# LWK2_MainBoard_Rev_1.net
KiCad netlist of a schematic drawn in EAGLE
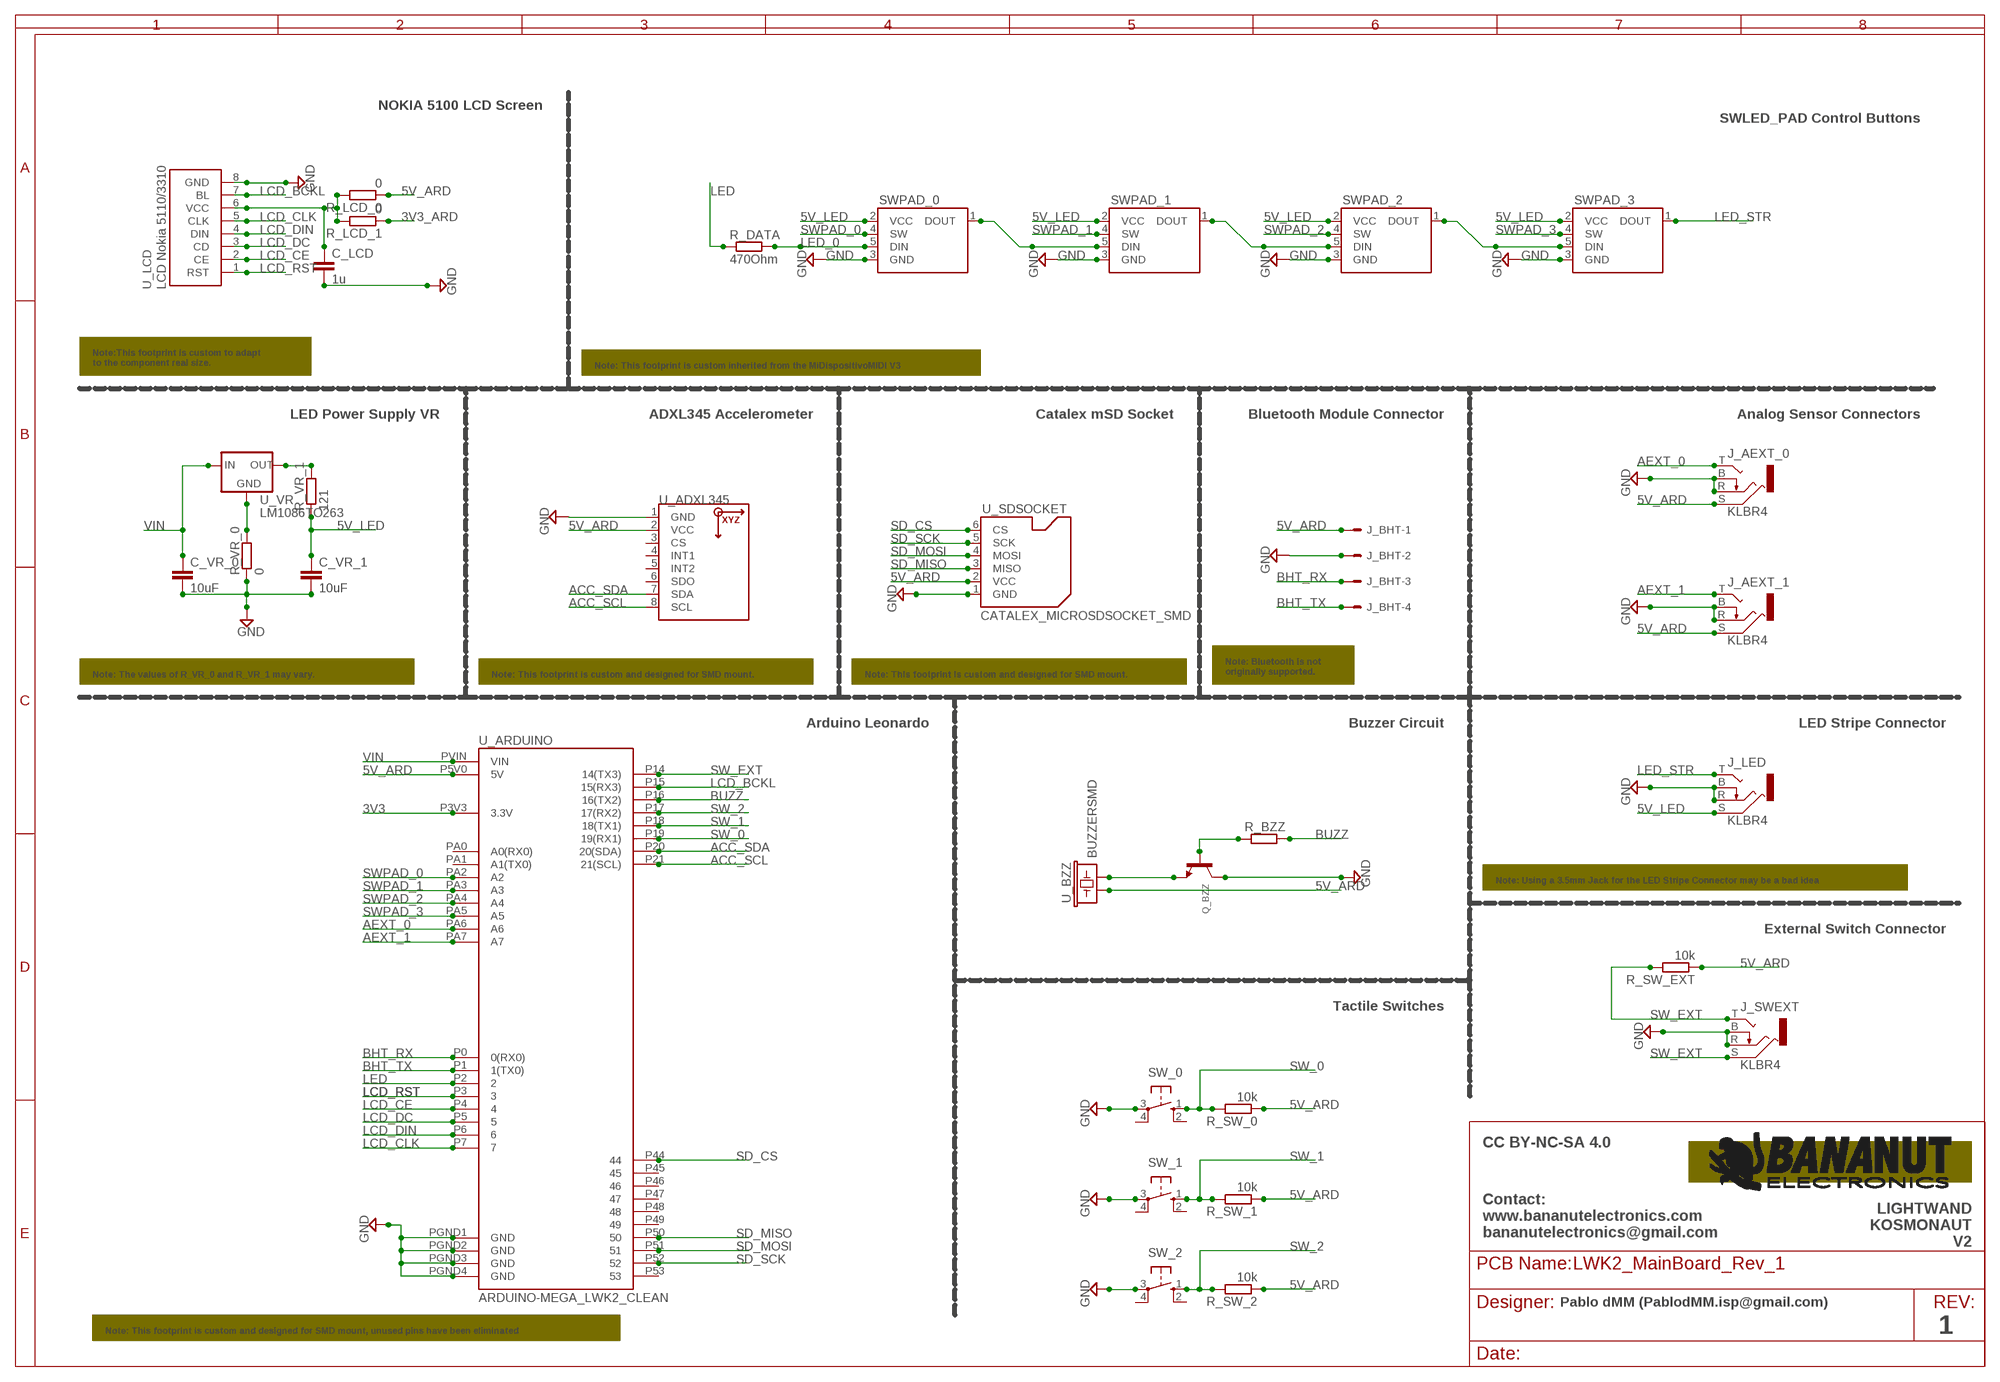
[diagram p0: schematic, sheet 1]

(export (version "E")
  (design (tool "Eeschema 10.0.6"))
  (components
    (comp (ref "C_LCD")
      (value "1u")
      (footprint "eagle-import:C1206")
      (libsource (lib "eagle-import") (part "C-EUC1206"))
    )
    (comp (ref "C_VR_0")
      (value "10uF")
      (footprint "eagle-import:C1206")
      (libsource (lib "eagle-import") (part "C-EUC1206"))
    )
    (comp (ref "C_VR_1")
      (value "10uF")
      (footprint "eagle-import:C1206")
      (libsource (lib "eagle-import") (part "C-EUC1206"))
    )
    (comp (ref "J_AEXT_0")
      (value "KLBR4")
      (footprint "eagle-import:KLBR4")
      (fields (field (name "MPN") "KLBR 4"))
      (libsource (lib "eagle-import") (part "KLBR4"))
    )
    (comp (ref "J_AEXT_1")
      (value "KLBR4")
      (footprint "eagle-import:KLBR4")
      (fields (field (name "MPN") "KLBR 4"))
      (libsource (lib "eagle-import") (part "KLBR4"))
    )
    (comp (ref "J_BHT")
      (value "22-05-7048-04")
      (footprint "eagle-import:7395-04")
      (libsource (lib "eagle-import") (part "22-?-0405-7048"))
    )
    (comp (ref "J_LED")
      (value "KLBR4")
      (footprint "eagle-import:KLBR4")
      (fields (field (name "MPN") "KLBR 4"))
      (libsource (lib "eagle-import") (part "KLBR4"))
    )
    (comp (ref "J_SWEXT")
      (value "KLBR4")
      (footprint "eagle-import:KLBR4")
      (fields (field (name "MPN") "KLBR 4"))
      (libsource (lib "eagle-import") (part "KLBR4"))
    )
    (comp (ref "Q_BZZ")
      (value "TRANSISTOR_NPNWIDE")
      (footprint "eagle-import:SOT23-WIDE")
      (libsource (lib "eagle-import") (part "TRANSISTOR_NPNWIDE"))
    )
    (comp (ref "R_BZZ")
      (value "R-EU_R1206")
      (footprint "eagle-import:R1206")
      (libsource (lib "eagle-import") (part "R-EU_R1206"))
    )
    (comp (ref "R_DATA")
      (value "470Ohm")
      (footprint "eagle-import:R1206")
      (libsource (lib "eagle-import") (part "R-EU_R1206"))
    )
    (comp (ref "R_LCD_0")
      (value "0")
      (footprint "eagle-import:R1206")
      (libsource (lib "eagle-import") (part "R-EU_R1206"))
    )
    (comp (ref "R_LCD_1")
      (value "0")
      (footprint "eagle-import:R1206")
      (libsource (lib "eagle-import") (part "R-EU_R1206"))
    )
    (comp (ref "R_SW_0")
      (value "10k")
      (footprint "eagle-import:R1206")
      (libsource (lib "eagle-import") (part "R-EU_R1206"))
    )
    (comp (ref "R_SW_1")
      (value "10k")
      (footprint "eagle-import:R1206")
      (libsource (lib "eagle-import") (part "R-EU_R1206"))
    )
    (comp (ref "R_SW_2")
      (value "10k")
      (footprint "eagle-import:R1206")
      (libsource (lib "eagle-import") (part "R-EU_R1206"))
    )
    (comp (ref "R_SW_EXT")
      (value "10k")
      (footprint "eagle-import:R1206")
      (libsource (lib "eagle-import") (part "R-EU_R1206"))
    )
    (comp (ref "R_VR_0")
      (value "0")
      (footprint "eagle-import:R1206")
      (libsource (lib "eagle-import") (part "R-EU_R1206"))
    )
    (comp (ref "R_VR_1")
      (value "121")
      (footprint "eagle-import:R1206")
      (libsource (lib "eagle-import") (part "R-EU_R1206"))
    )
    (comp (ref "SWPAD_0")
      (value "MDM_V3_LEDPAD")
      (footprint "eagle-import:MDM_V3_LEDPAD")
      (libsource (lib "eagle-import") (part "MDM_V3_LEDPAD"))
    )
    (comp (ref "SWPAD_1")
      (value "MDM_V3_LEDPAD")
      (footprint "eagle-import:MDM_V3_LEDPAD")
      (libsource (lib "eagle-import") (part "MDM_V3_LEDPAD"))
    )
    (comp (ref "SWPAD_2")
      (value "MDM_V3_LEDPAD")
      (footprint "eagle-import:MDM_V3_LEDPAD")
      (libsource (lib "eagle-import") (part "MDM_V3_LEDPAD"))
    )
    (comp (ref "SWPAD_3")
      (value "MDM_V3_LEDPAD")
      (footprint "eagle-import:MDM_V3_LEDPAD")
      (libsource (lib "eagle-import") (part "MDM_V3_LEDPAD"))
    )
    (comp (ref "SW_0")
      (value "40-XX-ROUND")
      (footprint "eagle-import:B3F-40XX-ROUND")
      (libsource (lib "eagle-import") (part "40-XX-ROUND"))
    )
    (comp (ref "SW_1")
      (value "40-XX-ROUND")
      (footprint "eagle-import:B3F-40XX-ROUND")
      (libsource (lib "eagle-import") (part "40-XX-ROUND"))
    )
    (comp (ref "SW_2")
      (value "40-XX-ROUND")
      (footprint "eagle-import:B3F-40XX-ROUND")
      (libsource (lib "eagle-import") (part "40-XX-ROUND"))
    )
    (comp (ref "U_ADXL345")
      (value "GY-291_ADXL345")
      (footprint "eagle-import:GY-291_ADXL345")
      (libsource (lib "eagle-import") (part "GY-291_ADXL345"))
    )
    (comp (ref "U_ARDUINO")
      (value "ARDUINO-MEGA_LWK2_CLEAN")
      (footprint "eagle-import:ARDUINO_MEGA_LWK2_CLEAN")
      (libsource (lib "eagle-import") (part "ARDUINO-MEGA_LWK2_CLEAN"))
    )
    (comp (ref "U_BZZ")
      (value "BUZZERSMD")
      (footprint "eagle-import:BUZZER-CMT1603")
      (libsource (lib "eagle-import") (part "BUZZERSMD"))
    )
    (comp (ref "U_LCD")
      (value "NOKIA5110")
      (footprint "eagle-import:NOKIA5110")
      (libsource (lib "eagle-import") (part "NOKIA5110"))
    )
    (comp (ref "U_SDSOCKET")
      (value "CATALEX_MICROSDSOCKET_SMD")
      (footprint "eagle-import:CATALEX_MICROSDSOCKET_SMD")
      (libsource (lib "eagle-import") (part "CATALEX_MICROSDSOCKET_SMD"))
    )
    (comp (ref "U_VR")
      (value "LM1086TO263")
      (footprint "eagle-import:TO263")
      (libsource (lib "eagle-import") (part "LM1086TO263"))
    )
  )
  (nets
    (net (code "1") (name "/3V3") (class "Default")
      (node (ref "U_ARDUINO") (pin "P3V3") (pinfunction "3.3V_P3V3") (pintype "bidirectional"))
    )
    (net (code "2") (name "/3V3_ARD") (class "Default")
      (node (ref "R_LCD_1") (pin "1") (pinfunction "1_1") (pintype "passive"))
    )
    (net (code "3") (name "/5V_ARD") (class "Default")
      (node (ref "J_AEXT_0") (pin "S") (pinfunction "S_S") (pintype "passive"))
      (node (ref "J_AEXT_1") (pin "S") (pinfunction "S_S") (pintype "passive"))
      (node (ref "J_BHT") (pin "1") (pinfunction "S_1") (pintype "passive"))
      (node (ref "R_LCD_0") (pin "1") (pinfunction "1_1") (pintype "passive"))
      (node (ref "R_SW_0") (pin "1") (pinfunction "1_1") (pintype "passive"))
      (node (ref "R_SW_1") (pin "1") (pinfunction "1_1") (pintype "passive"))
      (node (ref "R_SW_2") (pin "1") (pinfunction "1_1") (pintype "passive"))
      (node (ref "R_SW_EXT") (pin "1") (pinfunction "1_1") (pintype "passive"))
      (node (ref "U_ADXL345") (pin "2") (pinfunction "VCC_2") (pintype "output"))
      (node (ref "U_ARDUINO") (pin "P5V0") (pinfunction "5V_P5V0") (pintype "bidirectional"))
      (node (ref "U_BZZ") (pin "P$1") (pinfunction "1_P$1") (pintype "passive"))
      (node (ref "U_SDSOCKET") (pin "2") (pinfunction "VCC_2") (pintype "output"))
    )
    (net (code "4") (name "/5V_LED") (class "Default")
      (node (ref "C_VR_1") (pin "1") (pinfunction "1_1") (pintype "passive"))
      (node (ref "J_LED") (pin "S") (pinfunction "S_S") (pintype "passive"))
      (node (ref "R_VR_1") (pin "1") (pinfunction "1_1") (pintype "passive"))
      (node (ref "SWPAD_0") (pin "2") (pinfunction "VCC_2") (pintype "power_in"))
      (node (ref "SWPAD_1") (pin "2") (pinfunction "VCC_2") (pintype "power_in"))
      (node (ref "SWPAD_2") (pin "2") (pinfunction "VCC_2") (pintype "power_in"))
      (node (ref "SWPAD_3") (pin "2") (pinfunction "VCC_2") (pintype "power_in"))
    )
    (net (code "5") (name "/ACC_SCL") (class "Default")
      (node (ref "U_ADXL345") (pin "8") (pinfunction "SCL_8") (pintype "power_in"))
      (node (ref "U_ARDUINO") (pin "P21") (pinfunction "21(SCL)_P21") (pintype "bidirectional"))
    )
    (net (code "6") (name "/ACC_SDA") (class "Default")
      (node (ref "U_ADXL345") (pin "7") (pinfunction "SDA_7") (pintype "power_in"))
      (node (ref "U_ARDUINO") (pin "P20") (pinfunction "20(SDA)_P20") (pintype "bidirectional"))
    )
    (net (code "7") (name "/AEXT_0") (class "Default")
      (node (ref "J_AEXT_0") (pin "T") (pinfunction "T_T") (pintype "passive"))
      (node (ref "U_ARDUINO") (pin "PA6") (pinfunction "A6_PA6") (pintype "bidirectional"))
    )
    (net (code "8") (name "/AEXT_1") (class "Default")
      (node (ref "J_AEXT_1") (pin "T") (pinfunction "T_T") (pintype "passive"))
      (node (ref "U_ARDUINO") (pin "PA7") (pinfunction "A7_PA7") (pintype "bidirectional"))
    )
    (net (code "9") (name "/BHT_RX") (class "Default")
      (node (ref "J_BHT") (pin "3") (pinfunction "S_3") (pintype "passive"))
      (node (ref "U_ARDUINO") (pin "P0") (pinfunction "0(RX0)_P0") (pintype "bidirectional"))
    )
    (net (code "10") (name "/BHT_TX") (class "Default")
      (node (ref "J_BHT") (pin "4") (pinfunction "S_4") (pintype "passive"))
      (node (ref "U_ARDUINO") (pin "P1") (pinfunction "1(TX0)_P1") (pintype "bidirectional"))
    )
    (net (code "11") (name "/BUZZ") (class "Default")
      (node (ref "R_BZZ") (pin "2") (pinfunction "2_2") (pintype "passive"))
      (node (ref "U_ARDUINO") (pin "P16") (pinfunction "16(TX2)_P16") (pintype "bidirectional"))
    )
    (net (code "12") (name "/CS") (class "Default")
      (node (ref "U_ADXL345") (pin "3") (pinfunction "CS_3") (pintype "power_in"))
    )
    (net (code "13") (name "/INT1") (class "Default")
      (node (ref "U_ADXL345") (pin "4") (pinfunction "INT1_4") (pintype "power_in"))
    )
    (net (code "14") (name "/INT2") (class "Default")
      (node (ref "U_ADXL345") (pin "5") (pinfunction "INT2_5") (pintype "power_in"))
    )
    (net (code "15") (name "/LCD_BCKL") (class "Default")
      (node (ref "U_ARDUINO") (pin "P15") (pinfunction "15(RX3)_P15") (pintype "bidirectional"))
      (node (ref "U_LCD") (pin "7") (pinfunction "BL_7") (pintype "bidirectional"))
    )
    (net (code "16") (name "/LCD_CE") (class "Default")
      (node (ref "U_ARDUINO") (pin "P4") (pinfunction "4_P4") (pintype "bidirectional"))
      (node (ref "U_LCD") (pin "2") (pinfunction "CE_2") (pintype "bidirectional"))
    )
    (net (code "17") (name "/LCD_CLK") (class "Default")
      (node (ref "U_ARDUINO") (pin "P7") (pinfunction "7_P7") (pintype "bidirectional"))
      (node (ref "U_LCD") (pin "5") (pinfunction "CLK_5") (pintype "bidirectional"))
    )
    (net (code "18") (name "/LCD_DC") (class "Default")
      (node (ref "U_ARDUINO") (pin "P5") (pinfunction "5_P5") (pintype "bidirectional"))
      (node (ref "U_LCD") (pin "3") (pinfunction "CD_3") (pintype "bidirectional"))
    )
    (net (code "19") (name "/LCD_DIN") (class "Default")
      (node (ref "U_ARDUINO") (pin "P6") (pinfunction "6_P6") (pintype "bidirectional"))
      (node (ref "U_LCD") (pin "4") (pinfunction "DIN_4") (pintype "bidirectional"))
    )
    (net (code "20") (name "/LCD_RST") (class "Default")
      (node (ref "U_ARDUINO") (pin "P3") (pinfunction "3_P3") (pintype "bidirectional"))
      (node (ref "U_LCD") (pin "1") (pinfunction "RST_1") (pintype "bidirectional"))
    )
    (net (code "21") (name "/LED") (class "Default")
      (node (ref "R_DATA") (pin "1") (pinfunction "1_1") (pintype "passive"))
      (node (ref "U_ARDUINO") (pin "P2") (pinfunction "2_P2") (pintype "bidirectional"))
    )
    (net (code "22") (name "/LED_0") (class "Default")
      (node (ref "R_DATA") (pin "2") (pinfunction "2_2") (pintype "passive"))
      (node (ref "SWPAD_0") (pin "5") (pinfunction "DIN_5") (pintype "input"))
    )
    (net (code "23") (name "/LED_STR") (class "Default")
      (node (ref "J_LED") (pin "T") (pinfunction "T_T") (pintype "passive"))
      (node (ref "SWPAD_3") (pin "1") (pinfunction "DOUT_1") (pintype "output"))
    )
    (net (code "24") (name "/SDO") (class "Default")
      (node (ref "U_ADXL345") (pin "6") (pinfunction "SDO_6") (pintype "power_in"))
    )
    (net (code "25") (name "/SD_CS") (class "Default")
      (node (ref "U_ARDUINO") (pin "P44") (pinfunction "44_P44") (pintype "bidirectional"))
      (node (ref "U_SDSOCKET") (pin "6") (pinfunction "CS_6") (pintype "power_in"))
    )
    (net (code "26") (name "/SD_MISO") (class "Default")
      (node (ref "U_ARDUINO") (pin "P50") (pinfunction "50_P50") (pintype "bidirectional"))
      (node (ref "U_SDSOCKET") (pin "3") (pinfunction "MISO_3") (pintype "power_in"))
    )
    (net (code "27") (name "/SD_MOSI") (class "Default")
      (node (ref "U_ARDUINO") (pin "P51") (pinfunction "51_P51") (pintype "bidirectional"))
      (node (ref "U_SDSOCKET") (pin "4") (pinfunction "MOSI_4") (pintype "input"))
    )
    (net (code "28") (name "/SD_SCK") (class "Default")
      (node (ref "U_ARDUINO") (pin "P52") (pinfunction "52_P52") (pintype "bidirectional"))
      (node (ref "U_SDSOCKET") (pin "5") (pinfunction "SCK_5") (pintype "input"))
    )
    (net (code "29") (name "/SWPAD_0") (class "Default")
      (node (ref "SWPAD_0") (pin "4") (pinfunction "SW_4") (pintype "input"))
      (node (ref "U_ARDUINO") (pin "PA2") (pinfunction "A2_PA2") (pintype "bidirectional"))
    )
    (net (code "30") (name "/SWPAD_1") (class "Default")
      (node (ref "SWPAD_1") (pin "4") (pinfunction "SW_4") (pintype "input"))
      (node (ref "U_ARDUINO") (pin "PA3") (pinfunction "A3_PA3") (pintype "bidirectional"))
    )
    (net (code "31") (name "/SWPAD_2") (class "Default")
      (node (ref "SWPAD_2") (pin "4") (pinfunction "SW_4") (pintype "input"))
      (node (ref "U_ARDUINO") (pin "PA4") (pinfunction "A4_PA4") (pintype "bidirectional"))
    )
    (net (code "32") (name "/SWPAD_3") (class "Default")
      (node (ref "SWPAD_3") (pin "4") (pinfunction "SW_4") (pintype "input"))
      (node (ref "U_ARDUINO") (pin "PA5") (pinfunction "A5_PA5") (pintype "bidirectional"))
    )
    (net (code "33") (name "/SW_0") (class "Default")
      (node (ref "R_SW_0") (pin "2") (pinfunction "2_2") (pintype "passive"))
      (node (ref "SW_0") (pin "1") (pinfunction "S_1") (pintype "passive"))
      (node (ref "U_ARDUINO") (pin "P19") (pinfunction "19(RX1)_P19") (pintype "bidirectional"))
    )
    (net (code "34") (name "/SW_1") (class "Default")
      (node (ref "R_SW_1") (pin "2") (pinfunction "2_2") (pintype "passive"))
      (node (ref "SW_1") (pin "1") (pinfunction "S_1") (pintype "passive"))
      (node (ref "U_ARDUINO") (pin "P18") (pinfunction "18(TX1)_P18") (pintype "bidirectional"))
    )
    (net (code "35") (name "/SW_2") (class "Default")
      (node (ref "R_SW_2") (pin "2") (pinfunction "2_2") (pintype "passive"))
      (node (ref "SW_2") (pin "1") (pinfunction "S_1") (pintype "passive"))
      (node (ref "U_ARDUINO") (pin "P17") (pinfunction "17(RX2)_P17") (pintype "bidirectional"))
    )
    (net (code "36") (name "/SW_EXT") (class "Default")
      (node (ref "J_SWEXT") (pin "S") (pinfunction "S_S") (pintype "passive"))
      (node (ref "J_SWEXT") (pin "T") (pinfunction "T_T") (pintype "passive"))
      (node (ref "R_SW_EXT") (pin "2") (pinfunction "2_2") (pintype "passive"))
      (node (ref "U_ARDUINO") (pin "P14") (pinfunction "14(TX3)_P14") (pintype "bidirectional"))
    )
    (net (code "37") (name "/VIN") (class "Default")
      (node (ref "C_VR_0") (pin "1") (pinfunction "1_1") (pintype "passive"))
      (node (ref "U_ARDUINO") (pin "PVIN") (pinfunction "VIN_PVIN") (pintype "bidirectional"))
      (node (ref "U_VR") (pin "3") (pinfunction "IN_3") (pintype "input"))
    )
    (net (code "38") (name "GND") (class "Default")
      (node (ref "C_LCD") (pin "2") (pinfunction "2_2") (pintype "passive"))
      (node (ref "C_VR_0") (pin "2") (pinfunction "2_2") (pintype "passive"))
      (node (ref "C_VR_1") (pin "2") (pinfunction "2_2") (pintype "passive"))
      (node (ref "J_AEXT_0") (pin "B") (pinfunction "B_B") (pintype "passive"))
      (node (ref "J_AEXT_0") (pin "R") (pinfunction "R_R") (pintype "passive"))
      (node (ref "J_AEXT_1") (pin "B") (pinfunction "B_B") (pintype "passive"))
      (node (ref "J_AEXT_1") (pin "R") (pinfunction "R_R") (pintype "passive"))
      (node (ref "J_BHT") (pin "2") (pinfunction "S_2") (pintype "passive"))
      (node (ref "J_LED") (pin "B") (pinfunction "B_B") (pintype "passive"))
      (node (ref "J_LED") (pin "R") (pinfunction "R_R") (pintype "passive"))
      (node (ref "J_SWEXT") (pin "B") (pinfunction "B_B") (pintype "passive"))
      (node (ref "J_SWEXT") (pin "R") (pinfunction "R_R") (pintype "passive"))
      (node (ref "Q_BZZ") (pin "3") (pinfunction "C_3") (pintype "passive"))
      (node (ref "R_VR_0") (pin "1") (pinfunction "1_1") (pintype "passive"))
      (node (ref "SWPAD_0") (pin "3") (pinfunction "GND_3") (pintype "power_in"))
      (node (ref "SWPAD_1") (pin "3") (pinfunction "GND_3") (pintype "power_in"))
      (node (ref "SWPAD_2") (pin "3") (pinfunction "GND_3") (pintype "power_in"))
      (node (ref "SWPAD_3") (pin "3") (pinfunction "GND_3") (pintype "power_in"))
      (node (ref "SW_0") (pin "3") (pinfunction "P_3") (pintype "passive"))
      (node (ref "SW_1") (pin "3") (pinfunction "P_3") (pintype "passive"))
      (node (ref "SW_2") (pin "3") (pinfunction "P_3") (pintype "passive"))
      (node (ref "U_ADXL345") (pin "1") (pinfunction "GND_1") (pintype "output"))
      (node (ref "U_ARDUINO") (pin "PGND1") (pinfunction "GND_PGND1") (pintype "bidirectional"))
      (node (ref "U_ARDUINO") (pin "PGND2") (pinfunction "GND_PGND2") (pintype "bidirectional"))
      (node (ref "U_ARDUINO") (pin "PGND3") (pinfunction "GND_PGND3") (pintype "bidirectional"))
      (node (ref "U_ARDUINO") (pin "PGND4") (pinfunction "GND_PGND4") (pintype "bidirectional"))
      (node (ref "U_LCD") (pin "8") (pinfunction "GND_8") (pintype "power_in"))
      (node (ref "U_SDSOCKET") (pin "1") (pinfunction "GND_1") (pintype "output"))
    )
    (net (code "39") (name "Net-(Q_BZZ-B)") (class "Default")
      (node (ref "Q_BZZ") (pin "1") (pinfunction "B_1") (pintype "passive"))
      (node (ref "R_BZZ") (pin "1") (pinfunction "1_1") (pintype "passive"))
    )
    (net (code "40") (name "Net-(Q_BZZ-E)") (class "Default")
      (node (ref "Q_BZZ") (pin "2") (pinfunction "E_2") (pintype "passive"))
      (node (ref "U_BZZ") (pin "P$2") (pinfunction "2_P$2") (pintype "passive"))
    )
    (net (code "41") (name "Net-(SWPAD_0-DOUT)") (class "Default")
      (node (ref "SWPAD_0") (pin "1") (pinfunction "DOUT_1") (pintype "output"))
      (node (ref "SWPAD_1") (pin "5") (pinfunction "DIN_5") (pintype "input"))
    )
    (net (code "42") (name "Net-(SWPAD_1-DOUT)") (class "Default")
      (node (ref "SWPAD_1") (pin "1") (pinfunction "DOUT_1") (pintype "output"))
      (node (ref "SWPAD_2") (pin "5") (pinfunction "DIN_5") (pintype "input"))
    )
    (net (code "43") (name "Net-(SWPAD_2-DOUT)") (class "Default")
      (node (ref "SWPAD_2") (pin "1") (pinfunction "DOUT_1") (pintype "output"))
      (node (ref "SWPAD_3") (pin "5") (pinfunction "DIN_5") (pintype "input"))
    )
    (net (code "44") (name "Net-(U_LCD-VCC)") (class "Default")
      (node (ref "C_LCD") (pin "1") (pinfunction "1_1") (pintype "passive"))
      (node (ref "R_LCD_0") (pin "2") (pinfunction "2_2") (pintype "passive"))
      (node (ref "R_LCD_1") (pin "2") (pinfunction "2_2") (pintype "passive"))
      (node (ref "U_LCD") (pin "6") (pinfunction "VCC_6") (pintype "power_in"))
    )
    (net (code "45") (name "Net-(U_VR-GND)") (class "Default")
      (node (ref "R_VR_0") (pin "2") (pinfunction "2_2") (pintype "passive"))
      (node (ref "U_VR") (pin "1") (pinfunction "GND_1") (pintype "input"))
    )
    (net (code "46") (name "Net-(U_VR-OUT)") (class "Default")
      (node (ref "R_VR_1") (pin "2") (pinfunction "2_2") (pintype "passive"))
      (node (ref "U_VR") (pin "2") (pinfunction "OUT_2") (pintype "passive"))
    )
    (net (code "47") (name "unconnected-(SW_0-P1-Pad4)") (class "Default")
      (node (ref "SW_0") (pin "4") (pinfunction "P1_4") (pintype "passive"))
    )
    (net (code "48") (name "unconnected-(SW_0-S1-Pad2)") (class "Default")
      (node (ref "SW_0") (pin "2") (pinfunction "S1_2") (pintype "passive"))
    )
    (net (code "49") (name "unconnected-(SW_1-P1-Pad4)") (class "Default")
      (node (ref "SW_1") (pin "4") (pinfunction "P1_4") (pintype "passive"))
    )
    (net (code "50") (name "unconnected-(SW_1-S1-Pad2)") (class "Default")
      (node (ref "SW_1") (pin "2") (pinfunction "S1_2") (pintype "passive"))
    )
    (net (code "51") (name "unconnected-(SW_2-P1-Pad4)") (class "Default")
      (node (ref "SW_2") (pin "4") (pinfunction "P1_4") (pintype "passive"))
    )
    (net (code "52") (name "unconnected-(SW_2-S1-Pad2)") (class "Default")
      (node (ref "SW_2") (pin "2") (pinfunction "S1_2") (pintype "passive"))
    )
    (net (code "53") (name "unconnected-(U_ARDUINO-45-PadP45)") (class "Default")
      (node (ref "U_ARDUINO") (pin "P45") (pinfunction "45_P45") (pintype "bidirectional"))
    )
    (net (code "54") (name "unconnected-(U_ARDUINO-46-PadP46)") (class "Default")
      (node (ref "U_ARDUINO") (pin "P46") (pinfunction "46_P46") (pintype "bidirectional"))
    )
    (net (code "55") (name "unconnected-(U_ARDUINO-47-PadP47)") (class "Default")
      (node (ref "U_ARDUINO") (pin "P47") (pinfunction "47_P47") (pintype "bidirectional"))
    )
    (net (code "56") (name "unconnected-(U_ARDUINO-48-PadP48)") (class "Default")
      (node (ref "U_ARDUINO") (pin "P48") (pinfunction "48_P48") (pintype "bidirectional"))
    )
    (net (code "57") (name "unconnected-(U_ARDUINO-49-PadP49)") (class "Default")
      (node (ref "U_ARDUINO") (pin "P49") (pinfunction "49_P49") (pintype "bidirectional"))
    )
    (net (code "58") (name "unconnected-(U_ARDUINO-53-PadP53)") (class "Default")
      (node (ref "U_ARDUINO") (pin "P53") (pinfunction "53_P53") (pintype "bidirectional"))
    )
    (net (code "59") (name "unconnected-(U_ARDUINO-A0(RX0)-PadPA0)") (class "Default")
      (node (ref "U_ARDUINO") (pin "PA0") (pinfunction "A0(RX0)_PA0") (pintype "bidirectional"))
    )
    (net (code "60") (name "unconnected-(U_ARDUINO-A1(TX0)-PadPA1)") (class "Default")
      (node (ref "U_ARDUINO") (pin "PA1") (pinfunction "A1(TX0)_PA1") (pintype "bidirectional"))
    )
  )
)
